# Motor15m_Transistor.net
KiCad netlist of a schematic drawn in EAGLE
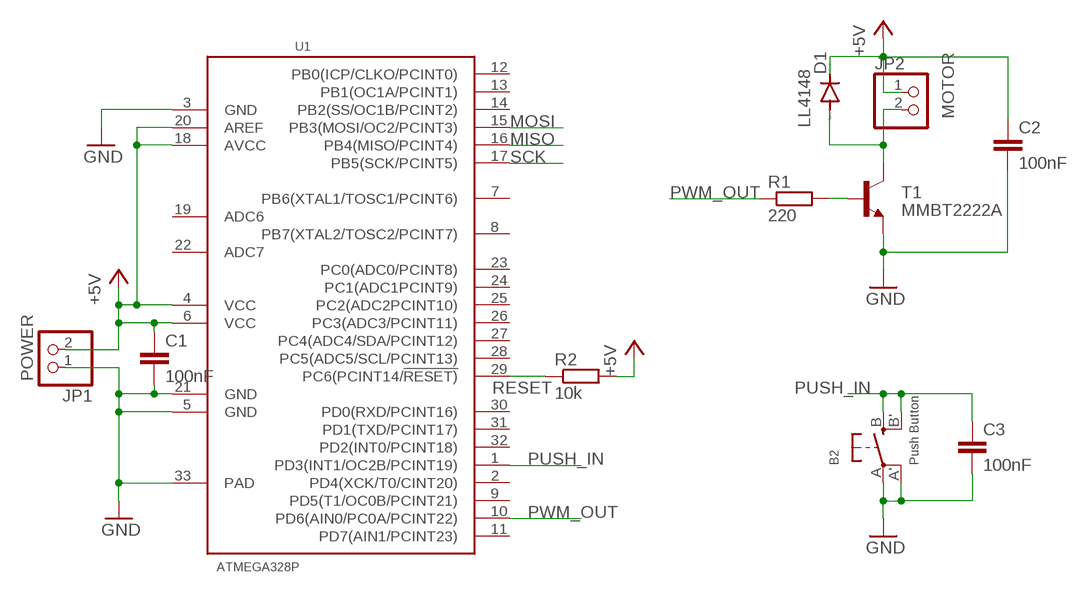
[diagram p0: schematic, sheet 1]

(export (version "E")
  (design (tool "Eeschema 10.0.6"))
  (components
    (comp (ref "B2")
      (value "Push Button")
      (footprint "eagle-import:EVQ-Q2")
      (libsource (lib "eagle-import") (part "SWITCH_TACT_SMT"))
    )
    (comp (ref "C1")
      (value "100nF")
      (footprint "eagle-import:C0805")
      (libsource (lib "eagle-import") (part "C-EUC0805"))
    )
    (comp (ref "C2")
      (value "100nF")
      (footprint "eagle-import:C0805")
      (libsource (lib "eagle-import") (part "C-EUC0805"))
    )
    (comp (ref "C3")
      (value "100nF")
      (footprint "eagle-import:C0805")
      (libsource (lib "eagle-import") (part "C-EUC0805"))
    )
    (comp (ref "D1")
      (value "LL4148")
      (footprint "eagle-import:SOD80C")
      (libsource (lib "eagle-import") (part "DIODE-SOD80C"))
    )
    (comp (ref "JP1")
      (value "POWER")
      (footprint "eagle-import:1X02_90")
      (libsource (lib "eagle-import") (part "PINHD-1X2/90"))
    )
    (comp (ref "JP2")
      (value "MOTOR")
      (footprint "eagle-import:1X02_90")
      (libsource (lib "eagle-import") (part "PINHD-1X2/90"))
    )
    (comp (ref "R1")
      (value "220")
      (footprint "eagle-import:R0603")
      (libsource (lib "eagle-import") (part "R-EU_R0603"))
    )
    (comp (ref "R2")
      (value "10k")
      (footprint "eagle-import:R0603")
      (libsource (lib "eagle-import") (part "R-EU_R0603"))
    )
    (comp (ref "T1")
      (value "MMBT2222A")
      (footprint "eagle-import:SOT23-BEC")
      (libsource (lib "eagle-import") (part "-NPN-SOT23-BECMMBT2222ALT1"))
    )
    (comp (ref "U1")
      (value "ATMEGA328P")
      (footprint "eagle-import:QFN32G-0.5-5X5MM")
      (fields (field (name "MPN") "ATMEGA328P-MU"))
      (libsource (lib "eagle-import") (part "MCU-ATMEGA328P-MU(QFN32)"))
    )
  )
  (nets
    (net (code "1") (name "+5V") (class "Default")
      (node (ref "C1") (pin "1") (pinfunction "1_1") (pintype "passive"))
      (node (ref "C2") (pin "1") (pinfunction "1_1") (pintype "passive"))
      (node (ref "D1") (pin "C") (pinfunction "C_C") (pintype "passive"))
      (node (ref "JP1") (pin "2") (pinfunction "2_2") (pintype "passive"))
      (node (ref "JP2") (pin "1") (pinfunction "1_1") (pintype "passive"))
      (node (ref "R2") (pin "2") (pinfunction "2_2") (pintype "passive"))
      (node (ref "U1") (pin "18") (pinfunction "AVCC_18") (pintype "bidirectional"))
      (node (ref "U1") (pin "20") (pinfunction "AREF_20") (pintype "bidirectional"))
      (node (ref "U1") (pin "4") (pinfunction "VCC_4") (pintype "bidirectional"))
      (node (ref "U1") (pin "6") (pinfunction "VCC_6") (pintype "bidirectional"))
    )
    (net (code "2") (name "/MISO") (class "Default")
      (node (ref "U1") (pin "16") (pinfunction "PB4(MISO/PCINT4)_16") (pintype "bidirectional"))
    )
    (net (code "3") (name "/MOSI") (class "Default")
      (node (ref "U1") (pin "15") (pinfunction "PB3(MOSI/OC2/PCINT3)_15") (pintype "bidirectional"))
    )
    (net (code "4") (name "/PUSH_IN") (class "Default")
      (node (ref "B2") (pin "B") (pinfunction "S_B") (pintype "passive"))
      (node (ref "B2") (pin "B'") (pinfunction "S1_B'") (pintype "passive"))
      (node (ref "C3") (pin "1") (pinfunction "1_1") (pintype "passive"))
      (node (ref "U1") (pin "1") (pinfunction "PD3(INT1/OC2B/PCINT19)_1") (pintype "bidirectional"))
    )
    (net (code "5") (name "/PWM_OUT") (class "Default")
      (node (ref "R1") (pin "1") (pinfunction "1_1") (pintype "passive"))
      (node (ref "U1") (pin "10") (pinfunction "PD6(AIN0/PC0A/PCINT22)_10") (pintype "bidirectional"))
    )
    (net (code "6") (name "/RESET") (class "Default")
      (node (ref "R2") (pin "1") (pinfunction "1_1") (pintype "passive"))
      (node (ref "U1") (pin "29") (pinfunction "PC6(PCINT14/~{RESET})_29") (pintype "bidirectional"))
    )
    (net (code "7") (name "/SCK") (class "Default")
      (node (ref "U1") (pin "17") (pinfunction "PB5(SCK/PCINT5)_17") (pintype "bidirectional"))
    )
    (net (code "8") (name "GND") (class "Default")
      (node (ref "B2") (pin "A") (pinfunction "P_A") (pintype "passive"))
      (node (ref "B2") (pin "A'") (pinfunction "P1_A'") (pintype "passive"))
      (node (ref "C1") (pin "2") (pinfunction "2_2") (pintype "passive"))
      (node (ref "C2") (pin "2") (pinfunction "2_2") (pintype "passive"))
      (node (ref "C3") (pin "2") (pinfunction "2_2") (pintype "passive"))
      (node (ref "JP1") (pin "1") (pinfunction "1_1") (pintype "passive"))
      (node (ref "T1") (pin "E") (pinfunction "E_E") (pintype "passive"))
      (node (ref "U1") (pin "21") (pinfunction "GND_21") (pintype "bidirectional"))
      (node (ref "U1") (pin "3") (pinfunction "GND_3") (pintype "bidirectional"))
      (node (ref "U1") (pin "33") (pinfunction "PAD_33") (pintype "bidirectional"))
      (node (ref "U1") (pin "5") (pinfunction "GND_5") (pintype "bidirectional"))
    )
    (net (code "9") (name "Net-(D1-PadA)") (class "Default")
      (node (ref "D1") (pin "A") (pinfunction "A_A") (pintype "passive"))
      (node (ref "JP2") (pin "2") (pinfunction "2_2") (pintype "passive"))
      (node (ref "T1") (pin "C") (pinfunction "C_C") (pintype "passive"))
    )
    (net (code "10") (name "Net-(R1-Pad2)") (class "Default")
      (node (ref "R1") (pin "2") (pinfunction "2_2") (pintype "passive"))
      (node (ref "T1") (pin "B") (pinfunction "B_B") (pintype "passive"))
    )
    (net (code "11") (name "unconnected-(U1-ADC6-Pad19)") (class "Default")
      (node (ref "U1") (pin "19") (pinfunction "ADC6_19") (pintype "bidirectional"))
    )
    (net (code "12") (name "unconnected-(U1-ADC7-Pad22)") (class "Default")
      (node (ref "U1") (pin "22") (pinfunction "ADC7_22") (pintype "bidirectional"))
    )
    (net (code "13") (name "unconnected-(U1-PB0(ICP{slash}CLKO{slash}PCINT0)-Pad12)") (class "Default")
      (node (ref "U1") (pin "12") (pinfunction "PB0(ICP/CLKO/PCINT0)_12") (pintype "bidirectional"))
    )
    (net (code "14") (name "unconnected-(U1-PB1(OC1A{slash}PCINT1)-Pad13)") (class "Default")
      (node (ref "U1") (pin "13") (pinfunction "PB1(OC1A/PCINT1)_13") (pintype "bidirectional"))
    )
    (net (code "15") (name "unconnected-(U1-PB2(SS{slash}OC1B{slash}PCINT2)-Pad14)") (class "Default")
      (node (ref "U1") (pin "14") (pinfunction "PB2(SS/OC1B/PCINT2)_14") (pintype "bidirectional"))
    )
    (net (code "16") (name "unconnected-(U1-PB6(XTAL1{slash}TOSC1{slash}PCINT6)-Pad7)") (class "Default")
      (node (ref "U1") (pin "7") (pinfunction "PB6(XTAL1/TOSC1/PCINT6)_7") (pintype "bidirectional"))
    )
    (net (code "17") (name "unconnected-(U1-PB7(XTAL2{slash}TOSC2{slash}PCINT7)-Pad8)") (class "Default")
      (node (ref "U1") (pin "8") (pinfunction "PB7(XTAL2/TOSC2/PCINT7)_8") (pintype "bidirectional"))
    )
    (net (code "18") (name "unconnected-(U1-PC0(ADC0{slash}PCINT8)-Pad23)") (class "Default")
      (node (ref "U1") (pin "23") (pinfunction "PC0(ADC0/PCINT8)_23") (pintype "bidirectional"))
    )
    (net (code "19") (name "unconnected-(U1-PC1(ADC1PCINT9)-Pad24)") (class "Default")
      (node (ref "U1") (pin "24") (pinfunction "PC1(ADC1PCINT9)_24") (pintype "bidirectional"))
    )
    (net (code "20") (name "unconnected-(U1-PC2(ADC2PCINT10)-Pad25)") (class "Default")
      (node (ref "U1") (pin "25") (pinfunction "PC2(ADC2PCINT10)_25") (pintype "bidirectional"))
    )
    (net (code "21") (name "unconnected-(U1-PC3(ADC3{slash}PCINT11)-Pad26)") (class "Default")
      (node (ref "U1") (pin "26") (pinfunction "PC3(ADC3/PCINT11)_26") (pintype "bidirectional"))
    )
    (net (code "22") (name "unconnected-(U1-PC4(ADC4{slash}SDA{slash}PCINT12)-Pad27)") (class "Default")
      (node (ref "U1") (pin "27") (pinfunction "PC4(ADC4/SDA/PCINT12)_27") (pintype "bidirectional"))
    )
    (net (code "23") (name "unconnected-(U1-PC5(ADC5{slash}SCL{slash}PCINT13)-Pad28)") (class "Default")
      (node (ref "U1") (pin "28") (pinfunction "PC5(ADC5/SCL/PCINT13)_28") (pintype "bidirectional"))
    )
    (net (code "24") (name "unconnected-(U1-PD0(RXD{slash}PCINT16)-Pad30)") (class "Default")
      (node (ref "U1") (pin "30") (pinfunction "PD0(RXD/PCINT16)_30") (pintype "bidirectional"))
    )
    (net (code "25") (name "unconnected-(U1-PD1(TXD{slash}PCINT17)-Pad31)") (class "Default")
      (node (ref "U1") (pin "31") (pinfunction "PD1(TXD/PCINT17)_31") (pintype "bidirectional"))
    )
    (net (code "26") (name "unconnected-(U1-PD2(INT0{slash}PCINT18)-Pad32)") (class "Default")
      (node (ref "U1") (pin "32") (pinfunction "PD2(INT0/PCINT18)_32") (pintype "bidirectional"))
    )
    (net (code "27") (name "unconnected-(U1-PD4(XCK{slash}T0{slash}CINT20)-Pad2)") (class "Default")
      (node (ref "U1") (pin "2") (pinfunction "PD4(XCK/T0/CINT20)_2") (pintype "bidirectional"))
    )
    (net (code "28") (name "unconnected-(U1-PD5(T1{slash}OC0B{slash}PCINT21)-Pad9)") (class "Default")
      (node (ref "U1") (pin "9") (pinfunction "PD5(T1/OC0B/PCINT21)_9") (pintype "bidirectional"))
    )
    (net (code "29") (name "unconnected-(U1-PD7(AIN1{slash}PCINT23)-Pad11)") (class "Default")
      (node (ref "U1") (pin "11") (pinfunction "PD7(AIN1/PCINT23)_11") (pintype "bidirectional"))
    )
  )
)
